# apex-iii-core.net
KiCad netlist of a schematic drawn in EAGLE
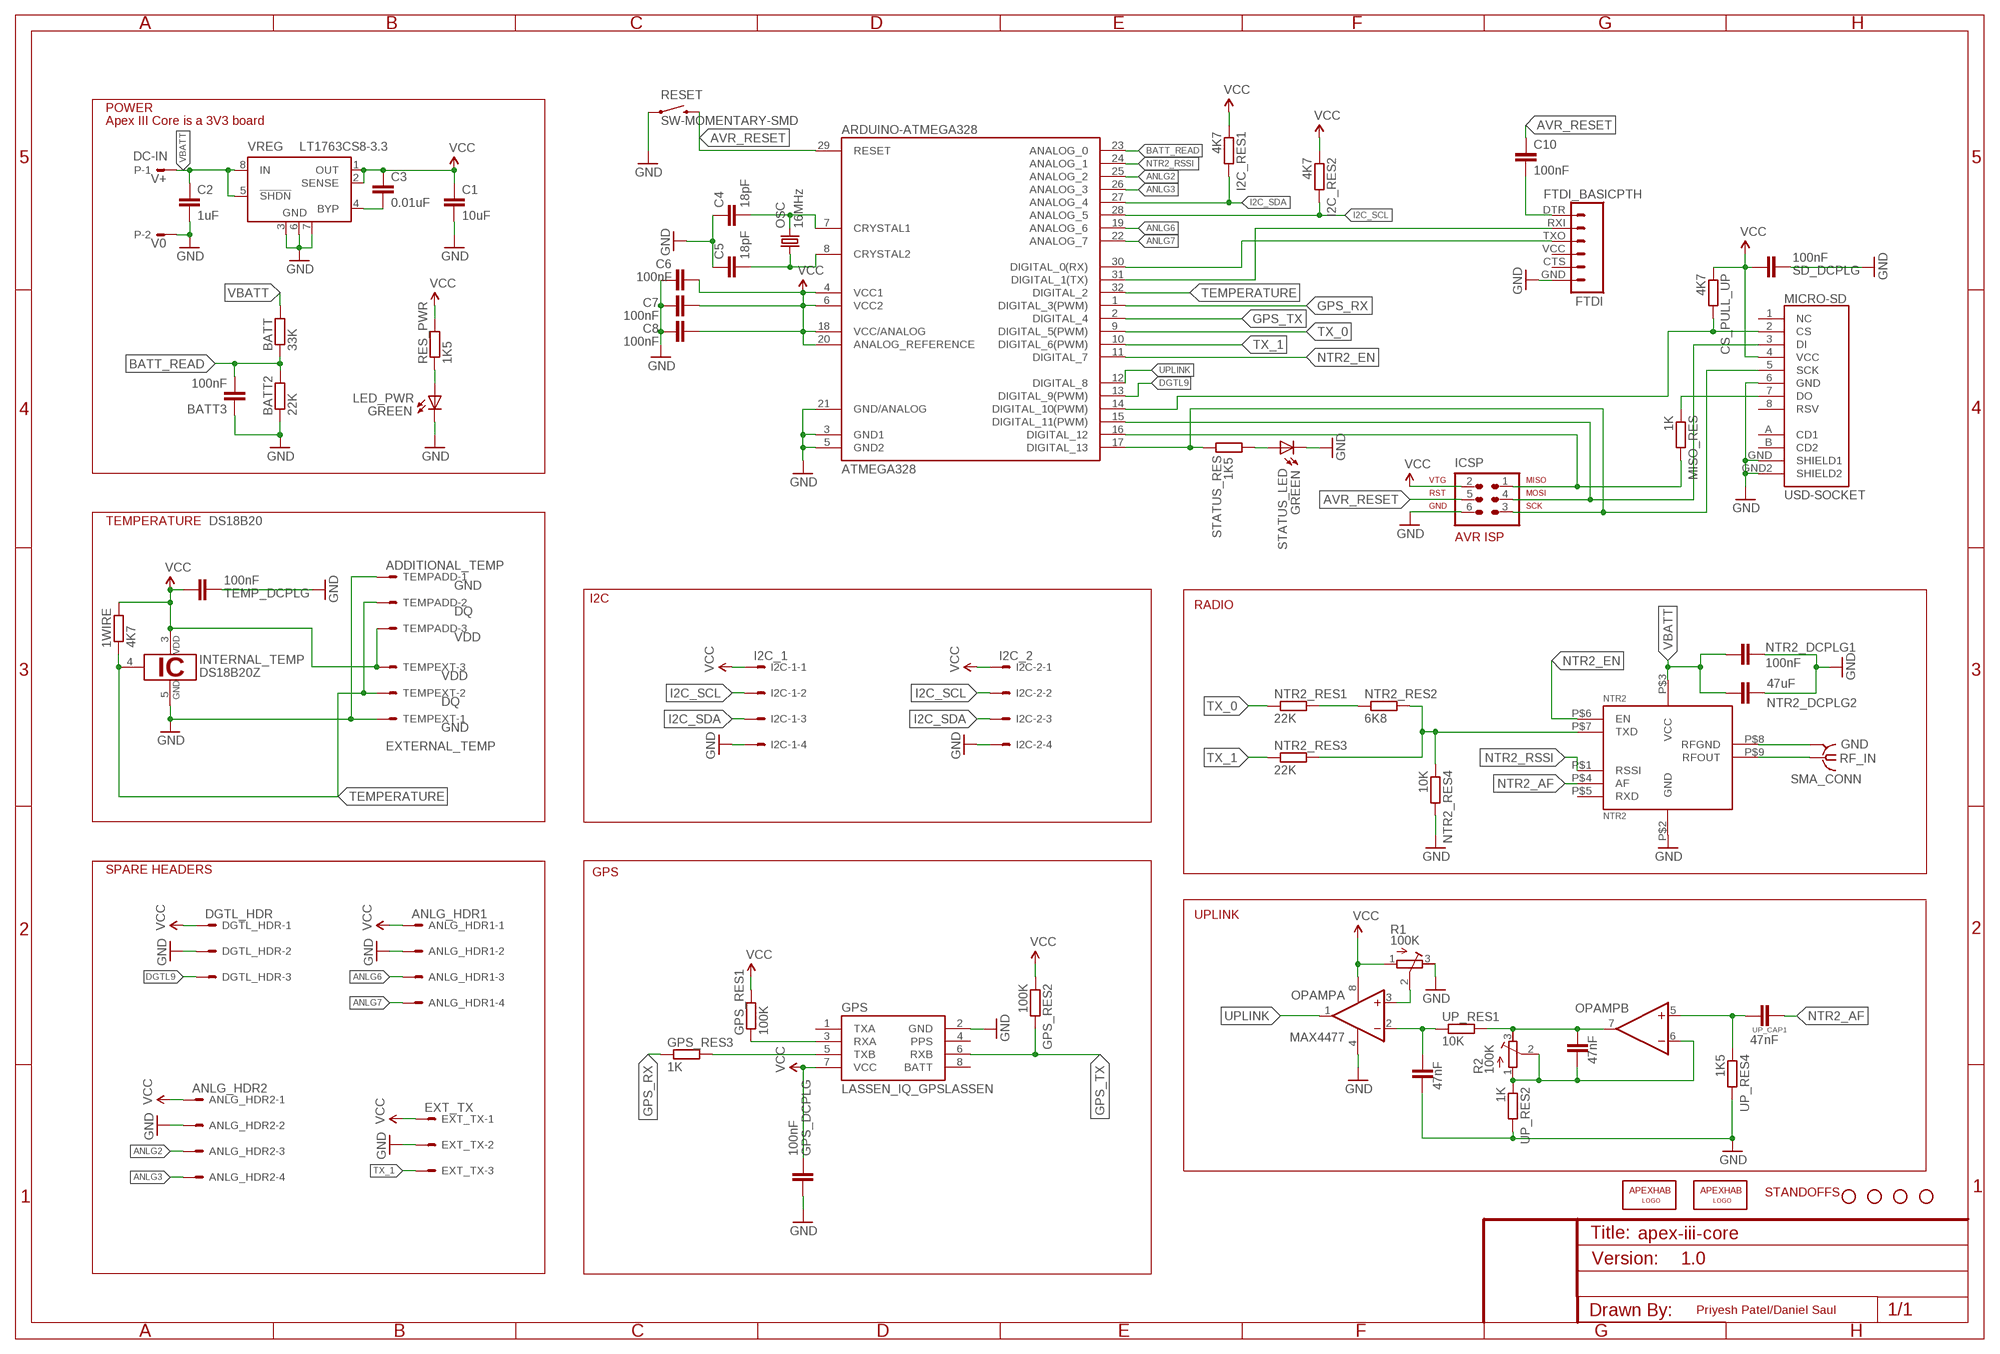
[diagram p0: schematic, sheet 1]

(export (version "E")
  (design (tool "Eeschema 10.0.6"))
  (components
    (comp (ref "1WIRE")
      (value "4K7")
      (footprint "eagle-import:R0805")
      (libsource (lib "eagle-import") (part "R-EU_R0805"))
    )
    (comp (ref "ANLG_HDR1")
      (value "ANLG_HDR1")
      (footprint "eagle-import:6410-04")
      (libsource (lib "eagle-import") (part "22-?-0427-2041"))
    )
    (comp (ref "ANLG_HDR2")
      (value "ANLG_HDR2")
      (footprint "eagle-import:6410-04")
      (libsource (lib "eagle-import") (part "22-?-0427-2041"))
    )
    (comp (ref "ARDUINO-ATMEGA328")
      (value "ATMEGA328")
      (footprint "eagle-import:TQFP32-08")
      (libsource (lib "eagle-import") (part "ATMEGA168-AU"))
    )
    (comp (ref "BATT")
      (value "33K")
      (footprint "eagle-import:R0805")
      (libsource (lib "eagle-import") (part "R-EU_R0805"))
    )
    (comp (ref "BATT2")
      (value "22K")
      (footprint "eagle-import:R0805")
      (libsource (lib "eagle-import") (part "R-EU_R0805"))
    )
    (comp (ref "BATT3")
      (value "100nF")
      (footprint "eagle-import:0805")
      (libsource (lib "eagle-import") (part "CAP0805"))
    )
    (comp (ref "C1")
      (value "10uF")
      (footprint "eagle-import:0805")
      (libsource (lib "eagle-import") (part "CAP0805"))
    )
    (comp (ref "C2")
      (value "1uF")
      (footprint "eagle-import:0805")
      (libsource (lib "eagle-import") (part "CAP0805"))
    )
    (comp (ref "C3")
      (value "0.01uF")
      (footprint "eagle-import:0805")
      (libsource (lib "eagle-import") (part "CAP0805"))
    )
    (comp (ref "C4")
      (value "18pF")
      (footprint "eagle-import:0805")
      (libsource (lib "eagle-import") (part "CAP0805"))
    )
    (comp (ref "C5")
      (value "18pF")
      (footprint "eagle-import:0805")
      (libsource (lib "eagle-import") (part "CAP0805"))
    )
    (comp (ref "C6")
      (value "100nF")
      (footprint "eagle-import:0805")
      (libsource (lib "eagle-import") (part "CAP0805"))
    )
    (comp (ref "C7")
      (value "100nF")
      (footprint "eagle-import:0805")
      (libsource (lib "eagle-import") (part "CAP0805"))
    )
    (comp (ref "C8")
      (value "100nF")
      (footprint "eagle-import:0805")
      (libsource (lib "eagle-import") (part "CAP0805"))
    )
    (comp (ref "C10")
      (value "100nF")
      (footprint "eagle-import:0805")
      (libsource (lib "eagle-import") (part "CAP0805"))
    )
    (comp (ref "CS_PULL_UP")
      (value "4K7")
      (footprint "eagle-import:R0805")
      (libsource (lib "eagle-import") (part "R-EU_R0805"))
    )
    (comp (ref "DGTL_HDR")
      (value "DGTL_HDR")
      (footprint "eagle-import:6410-03")
      (libsource (lib "eagle-import") (part "22-?-0327-2031"))
    )
    (comp (ref "EXT_TX")
      (value "EXT_TX")
      (footprint "eagle-import:6410-03")
      (libsource (lib "eagle-import") (part "22-?-0327-2031"))
    )
    (comp (ref "FTDI")
      (value "FTDI_BASICPTH")
      (footprint "eagle-import:FTDI_BASIC")
      (libsource (lib "eagle-import") (part "FTDI_BASICPTH"))
    )
    (comp (ref "GPS")
      (value "LASSEN_IQ_GPSLASSEN")
      (footprint "eagle-import:LASSEN_IQ_GPS")
      (libsource (lib "eagle-import") (part "LASSEN_IQ_GPSLASSEN"))
    )
    (comp (ref "GPS_DCPLG")
      (value "100nF")
      (footprint "eagle-import:0805")
      (libsource (lib "eagle-import") (part "CAP0805"))
    )
    (comp (ref "GPS_RES1")
      (value "100K")
      (footprint "eagle-import:R0805")
      (libsource (lib "eagle-import") (part "R-EU_R0805"))
    )
    (comp (ref "GPS_RES2")
      (value "100K")
      (footprint "eagle-import:R0805")
      (libsource (lib "eagle-import") (part "R-EU_R0805"))
    )
    (comp (ref "GPS_RES3")
      (value "1K")
      (footprint "eagle-import:R0805")
      (libsource (lib "eagle-import") (part "R-EU_R0805"))
    )
    (comp (ref "I2C-1")
      (value "I2C_1")
      (footprint "eagle-import:6410-04")
      (libsource (lib "eagle-import") (part "22-?-0427-2041"))
    )
    (comp (ref "I2C-2")
      (value "I2C_2")
      (footprint "eagle-import:6410-04")
      (libsource (lib "eagle-import") (part "22-?-0427-2041"))
    )
    (comp (ref "I2C_RES1")
      (value "4K7")
      (footprint "eagle-import:R0805")
      (libsource (lib "eagle-import") (part "R-EU_R0805"))
    )
    (comp (ref "I2C_RES2")
      (value "4K7")
      (footprint "eagle-import:R0805")
      (libsource (lib "eagle-import") (part "R-EU_R0805"))
    )
    (comp (ref "ICSP")
      (value "AVR-ISP-6")
      (footprint "eagle-import:AVR-ISP-6")
      (libsource (lib "eagle-import") (part "AVR-ISP-6"))
    )
    (comp (ref "INTERNAL_TEMP")
      (value "DS18B20Z")
      (footprint "eagle-import:SO08")
      (libsource (lib "eagle-import") (part "DS18B20Z"))
    )
    (comp (ref "JP1")
      (value "STAND-OFF")
      (footprint "eagle-import:STAND-OFF")
      (libsource (lib "eagle-import") (part "STAND-OFF"))
    )
    (comp (ref "JP2")
      (value "STAND-OFF")
      (footprint "eagle-import:STAND-OFF")
      (libsource (lib "eagle-import") (part "STAND-OFF"))
    )
    (comp (ref "JP3")
      (value "STAND-OFF")
      (footprint "eagle-import:STAND-OFF")
      (libsource (lib "eagle-import") (part "STAND-OFF"))
    )
    (comp (ref "JP4")
      (value "STAND-OFF")
      (footprint "eagle-import:STAND-OFF")
      (libsource (lib "eagle-import") (part "STAND-OFF"))
    )
    (comp (ref "JP5")
      (value "APEXHAB-LOGO_APEXHAB-SMALL")
      (footprint "eagle-import:APEXHAB-LOGO-SMALL")
      (libsource (lib "eagle-import") (part "APEXHAB-LOGO_APEXHAB-SMALL"))
    )
    (comp (ref "JP6")
      (value "APEXHAB-LOGO_APEXHAB")
      (footprint "eagle-import:APEXHAB-LOGO")
      (libsource (lib "eagle-import") (part "APEXHAB-LOGO_APEXHAB"))
    )
    (comp (ref "LED_PWR")
      (value "GREEN")
      (footprint "eagle-import:CHIPLED_0603")
      (libsource (lib "eagle-import") (part "LEDCHIPLED_0603"))
    )
    (comp (ref "MICRO-SD")
      (value "USD-SOCKET")
      (footprint "eagle-import:MICRO-SD-PUSH-PULL")
      (libsource (lib "eagle-import") (part "USD-SOCKET"))
    )
    (comp (ref "MISO_RES")
      (value "1K")
      (footprint "eagle-import:R0805")
      (libsource (lib "eagle-import") (part "R-EU_R0805"))
    )
    (comp (ref "NTR2")
      (value "NTR2")
      (footprint "eagle-import:NTR2")
      (libsource (lib "eagle-import") (part "NTR2"))
    )
    (comp (ref "NTR2_DCPLG1")
      (value "100nF")
      (footprint "eagle-import:0805")
      (libsource (lib "eagle-import") (part "CAP0805"))
    )
    (comp (ref "NTR2_DCPLG2")
      (value "47uF")
      (footprint "eagle-import:0805")
      (libsource (lib "eagle-import") (part "CAP0805"))
    )
    (comp (ref "NTR2_RES1")
      (value "22K")
      (footprint "eagle-import:R0805")
      (libsource (lib "eagle-import") (part "R-EU_R0805"))
    )
    (comp (ref "NTR2_RES2")
      (value "6K8")
      (footprint "eagle-import:R0805")
      (libsource (lib "eagle-import") (part "R-EU_R0805"))
    )
    (comp (ref "NTR2_RES3")
      (value "22K")
      (footprint "eagle-import:R0805")
      (libsource (lib "eagle-import") (part "R-EU_R0805"))
    )
    (comp (ref "NTR2_RES4")
      (value "10K")
      (footprint "eagle-import:R0805")
      (libsource (lib "eagle-import") (part "R-EU_R0805"))
    )
    (comp (ref "OPAMP")
      (value "MAX4477")
      (footprint "eagle-import:SO08")
      (libsource (lib "eagle-import") (part "CA3240ED"))
    )
    (comp (ref "OSC")
      (value "16MHz")
      (footprint "eagle-import:CRYSTAL-SMD-5X3")
      (libsource (lib "eagle-import") (part "CRYSTAL5X3"))
    )
    (comp (ref "P")
      (value "DC-IN")
      (footprint "eagle-import:6410-02")
      (libsource (lib "eagle-import") (part "22-?-0227-2021"))
    )
    (comp (ref "R1")
      (value "100K")
      (footprint "eagle-import:RTRIM3214W")
      (libsource (lib "eagle-import") (part "R-TRIMM3214W"))
    )
    (comp (ref "R2")
      (value "100K")
      (footprint "eagle-import:RTRIM3214W")
      (libsource (lib "eagle-import") (part "R-TRIMM3214W"))
    )
    (comp (ref "RESET")
      (value "SW-MOMENTARY-SMD")
      (footprint "eagle-import:TACTILE-SWITCH-1101NE")
      (libsource (lib "eagle-import") (part "SWITCH-MOMENTARY-2-SMD-1101NE"))
    )
    (comp (ref "RES_PWR")
      (value "1K5")
      (footprint "eagle-import:R0805")
      (libsource (lib "eagle-import") (part "R-EU_R0805"))
    )
    (comp (ref "SD_DCPLG")
      (value "100nF")
      (footprint "eagle-import:0805")
      (libsource (lib "eagle-import") (part "CAP0805"))
    )
    (comp (ref "SMA_CONN")
      (value "SMA-142-0701-801/806")
      (footprint "eagle-import:J502-ND-142-0701-801_806")
      (fields (field (name "MF") "JOHNSON COMPONENTS") (field (name "MPN") "142-0701-801"))
      (libsource (lib "eagle-import") (part "SMA-142-0701-801/806"))
    )
    (comp (ref "STATUS_LED")
      (value "GREEN")
      (footprint "eagle-import:CHIPLED_0603")
      (libsource (lib "eagle-import") (part "LEDCHIPLED_0603"))
    )
    (comp (ref "STATUS_RES")
      (value "1K5")
      (footprint "eagle-import:R0805")
      (libsource (lib "eagle-import") (part "R-EU_R0805"))
    )
    (comp (ref "TEMPADD")
      (value "ADDITIONAL_TEMP")
      (footprint "eagle-import:6410-03")
      (libsource (lib "eagle-import") (part "con-molex_22-?-0327-2031"))
    )
    (comp (ref "TEMPEXT")
      (value "EXTERNAL_TEMP")
      (footprint "eagle-import:6410-03")
      (libsource (lib "eagle-import") (part "con-molex_22-?-0327-2031"))
    )
    (comp (ref "TEMP_DCPLG")
      (value "100nF")
      (footprint "eagle-import:0805")
      (libsource (lib "eagle-import") (part "CAP0805"))
    )
    (comp (ref "UP_CAP1")
      (value "47nF")
      (footprint "eagle-import:0805")
      (libsource (lib "eagle-import") (part "CAP0805"))
    )
    (comp (ref "UP_CAP3")
      (value "47nF")
      (footprint "eagle-import:0805")
      (libsource (lib "eagle-import") (part "CAP0805"))
    )
    (comp (ref "UP_CAP4")
      (value "47nF")
      (footprint "eagle-import:0805")
      (libsource (lib "eagle-import") (part "CAP0805"))
    )
    (comp (ref "UP_RES1")
      (value "10K")
      (footprint "eagle-import:R0805")
      (libsource (lib "eagle-import") (part "R-EU_R0805"))
    )
    (comp (ref "UP_RES2")
      (value "1K")
      (footprint "eagle-import:R0805")
      (libsource (lib "eagle-import") (part "R-EU_R0805"))
    )
    (comp (ref "UP_RES4")
      (value "1K5")
      (footprint "eagle-import:R0805")
      (libsource (lib "eagle-import") (part "R-EU_R0805"))
    )
    (comp (ref "VREG")
      (value "LT1763CS8-3.3")
      (footprint "eagle-import:SOIC8")
      (libsource (lib "eagle-import") (part "LT1763CS8-3.3"))
    )
  )
  (nets
    (net (code "1") (name "/BATT") (class "Default")
      (node (ref "GPS") (pin "8") (pinfunction "BATT_8") (pintype "power_in"))
    )
    (net (code "2") (name "/RF_IN") (class "Default")
      (node (ref "NTR2") (pin "P$9") (pinfunction "RFOUT_P$9") (pintype "bidirectional"))
      (node (ref "SMA_CONN") (pin "1") (pinfunction "1_1") (pintype "passive"))
    )
    (net (code "3") (name "ANLG2") (class "Default")
      (node (ref "ANLG_HDR2") (pin "3") (pinfunction "S_3") (pintype "passive"))
      (node (ref "ARDUINO-ATMEGA328") (pin "25") (pinfunction "ANALOG_2_25") (pintype "bidirectional"))
    )
    (net (code "4") (name "ANLG3") (class "Default")
      (node (ref "ANLG_HDR2") (pin "4") (pinfunction "S_4") (pintype "passive"))
      (node (ref "ARDUINO-ATMEGA328") (pin "26") (pinfunction "ANALOG_3_26") (pintype "bidirectional"))
    )
    (net (code "5") (name "ANLG6") (class "Default")
      (node (ref "ANLG_HDR1") (pin "3") (pinfunction "S_3") (pintype "passive"))
      (node (ref "ARDUINO-ATMEGA328") (pin "19") (pinfunction "ANALOG_6_19") (pintype "passive"))
    )
    (net (code "6") (name "ANLG7") (class "Default")
      (node (ref "ANLG_HDR1") (pin "4") (pinfunction "S_4") (pintype "passive"))
      (node (ref "ARDUINO-ATMEGA328") (pin "22") (pinfunction "ANALOG_7_22") (pintype "passive"))
    )
    (net (code "7") (name "AVR_RESET") (class "Default")
      (node (ref "ARDUINO-ATMEGA328") (pin "29") (pinfunction "RESET_29") (pintype "bidirectional"))
      (node (ref "C10") (pin "1") (pinfunction "1_1") (pintype "passive"))
      (node (ref "ICSP") (pin "5") (pinfunction "5_5") (pintype "passive"))
      (node (ref "RESET") (pin "P$2") (pinfunction "2_P$2") (pintype "passive"))
    )
    (net (code "8") (name "BATT_READ") (class "Default")
      (node (ref "ARDUINO-ATMEGA328") (pin "23") (pinfunction "ANALOG_0_23") (pintype "bidirectional"))
      (node (ref "BATT") (pin "1") (pinfunction "1_1") (pintype "passive"))
      (node (ref "BATT2") (pin "2") (pinfunction "2_2") (pintype "passive"))
      (node (ref "BATT3") (pin "2") (pinfunction "2_2") (pintype "passive"))
    )
    (net (code "9") (name "DGTL9") (class "Default")
      (node (ref "ARDUINO-ATMEGA328") (pin "13") (pinfunction "DIGITAL_9(PWM)_13") (pintype "bidirectional"))
      (node (ref "DGTL_HDR") (pin "3") (pinfunction "S_3") (pintype "passive"))
    )
    (net (code "10") (name "GND") (class "Default")
      (node (ref "ANLG_HDR1") (pin "2") (pinfunction "S_2") (pintype "passive"))
      (node (ref "ANLG_HDR2") (pin "2") (pinfunction "S_2") (pintype "passive"))
      (node (ref "ARDUINO-ATMEGA328") (pin "21") (pinfunction "GND/ANALOG_21") (pintype "power_in"))
      (node (ref "ARDUINO-ATMEGA328") (pin "3") (pinfunction "GND1_3") (pintype "power_in"))
      (node (ref "ARDUINO-ATMEGA328") (pin "5") (pinfunction "GND2_5") (pintype "power_in"))
      (node (ref "BATT2") (pin "1") (pinfunction "1_1") (pintype "passive"))
      (node (ref "BATT3") (pin "1") (pinfunction "1_1") (pintype "passive"))
      (node (ref "C1") (pin "2") (pinfunction "2_2") (pintype "passive"))
      (node (ref "C2") (pin "2") (pinfunction "2_2") (pintype "passive"))
      (node (ref "C4") (pin "1") (pinfunction "1_1") (pintype "passive"))
      (node (ref "C5") (pin "1") (pinfunction "1_1") (pintype "passive"))
      (node (ref "C6") (pin "1") (pinfunction "1_1") (pintype "passive"))
      (node (ref "C7") (pin "1") (pinfunction "1_1") (pintype "passive"))
      (node (ref "C8") (pin "1") (pinfunction "1_1") (pintype "passive"))
      (node (ref "DGTL_HDR") (pin "2") (pinfunction "S_2") (pintype "passive"))
      (node (ref "EXT_TX") (pin "2") (pinfunction "S_2") (pintype "passive"))
      (node (ref "FTDI") (pin "GND") (pinfunction "6_GND") (pintype "passive"))
      (node (ref "GPS") (pin "2") (pinfunction "GND_2") (pintype "power_in"))
      (node (ref "GPS_DCPLG") (pin "2") (pinfunction "2_2") (pintype "passive"))
      (node (ref "I2C-1") (pin "4") (pinfunction "S_4") (pintype "passive"))
      (node (ref "I2C-2") (pin "4") (pinfunction "S_4") (pintype "passive"))
      (node (ref "ICSP") (pin "6") (pinfunction "6_6") (pintype "passive"))
      (node (ref "INTERNAL_TEMP") (pin "5") (pinfunction "GND_5") (pintype "power_in"))
      (node (ref "LED_PWR") (pin "C") (pinfunction "C_C") (pintype "passive"))
      (node (ref "MICRO-SD") (pin "6") (pinfunction "GND_6") (pintype "bidirectional"))
      (node (ref "MICRO-SD") (pin "GND") (pinfunction "SHIELD1_GND") (pintype "bidirectional"))
      (node (ref "MICRO-SD") (pin "GND2") (pinfunction "SHIELD2_GND2") (pintype "bidirectional"))
      (node (ref "NTR2") (pin "P$2") (pinfunction "GND_P$2") (pintype "power_in"))
      (node (ref "NTR2") (pin "P$8") (pinfunction "RFGND_P$8") (pintype "bidirectional"))
      (node (ref "NTR2_DCPLG1") (pin "1") (pinfunction "1_1") (pintype "passive"))
      (node (ref "NTR2_DCPLG2") (pin "1") (pinfunction "1_1") (pintype "passive"))
      (node (ref "NTR2_RES4") (pin "2") (pinfunction "2_2") (pintype "passive"))
      (node (ref "OPAMP") (pin "4") (pinfunction "V-_4") (pintype "power_in"))
      (node (ref "P") (pin "2") (pinfunction "S_2") (pintype "passive"))
      (node (ref "R1") (pin "3") (pinfunction "A_3") (pintype "passive"))
      (node (ref "RESET") (pin "P$1") (pinfunction "1_P$1") (pintype "passive"))
      (node (ref "SD_DCPLG") (pin "1") (pinfunction "1_1") (pintype "passive"))
      (node (ref "SMA_CONN") (pin "G@1") (pinfunction "GND_G@1") (pintype "power_in"))
      (node (ref "STATUS_LED") (pin "C") (pinfunction "C_C") (pintype "passive"))
      (node (ref "TEMPADD") (pin "1") (pinfunction "S_1") (pintype "passive"))
      (node (ref "TEMPEXT") (pin "1") (pinfunction "S_1") (pintype "passive"))
      (node (ref "TEMP_DCPLG") (pin "1") (pinfunction "1_1") (pintype "passive"))
      (node (ref "UP_CAP4") (pin "2") (pinfunction "2_2") (pintype "passive"))
      (node (ref "UP_RES2") (pin "2") (pinfunction "2_2") (pintype "passive"))
      (node (ref "UP_RES4") (pin "2") (pinfunction "2_2") (pintype "passive"))
      (node (ref "VREG") (pin "3") (pinfunction "GND_3") (pintype "power_in"))
      (node (ref "VREG") (pin "6") (pinfunction "GND_6") (pintype "power_in"))
      (node (ref "VREG") (pin "7") (pinfunction "GND_7") (pintype "power_in"))
    )
    (net (code "11") (name "GPS_RX") (class "Default")
      (node (ref "ARDUINO-ATMEGA328") (pin "1") (pinfunction "DIGITAL_3(PWM)_1") (pintype "bidirectional"))
      (node (ref "GPS_RES3") (pin "1") (pinfunction "1_1") (pintype "passive"))
    )
    (net (code "12") (name "GPS_TX") (class "Default")
      (node (ref "ARDUINO-ATMEGA328") (pin "2") (pinfunction "DIGITAL_4_2") (pintype "bidirectional"))
      (node (ref "GPS") (pin "6") (pinfunction "RXB_6") (pintype "input"))
      (node (ref "GPS_RES2") (pin "2") (pinfunction "2_2") (pintype "passive"))
    )
    (net (code "13") (name "I2C_SCL") (class "Default")
      (node (ref "ARDUINO-ATMEGA328") (pin "28") (pinfunction "ANALOG_5_28") (pintype "bidirectional"))
      (node (ref "I2C-1") (pin "2") (pinfunction "S_2") (pintype "passive"))
      (node (ref "I2C-2") (pin "2") (pinfunction "S_2") (pintype "passive"))
      (node (ref "I2C_RES2") (pin "2") (pinfunction "2_2") (pintype "passive"))
    )
    (net (code "14") (name "I2C_SDA") (class "Default")
      (node (ref "ARDUINO-ATMEGA328") (pin "27") (pinfunction "ANALOG_4_27") (pintype "bidirectional"))
      (node (ref "I2C-1") (pin "3") (pinfunction "S_3") (pintype "passive"))
      (node (ref "I2C-2") (pin "3") (pinfunction "S_3") (pintype "passive"))
      (node (ref "I2C_RES1") (pin "2") (pinfunction "2_2") (pintype "passive"))
    )
    (net (code "15") (name "NTR2_AF") (class "Default")
      (node (ref "NTR2") (pin "P$4") (pinfunction "AF_P$4") (pintype "bidirectional"))
      (node (ref "UP_CAP1") (pin "1") (pinfunction "1_1") (pintype "passive"))
    )
    (net (code "16") (name "NTR2_EN") (class "Default")
      (node (ref "ARDUINO-ATMEGA328") (pin "11") (pinfunction "DIGITAL_7_11") (pintype "bidirectional"))
      (node (ref "NTR2") (pin "P$6") (pinfunction "EN_P$6") (pintype "bidirectional"))
    )
    (net (code "17") (name "NTR2_RSSI") (class "Default")
      (node (ref "ARDUINO-ATMEGA328") (pin "24") (pinfunction "ANALOG_1_24") (pintype "bidirectional"))
      (node (ref "NTR2") (pin "P$1") (pinfunction "RSSI_P$1") (pintype "bidirectional"))
    )
    (net (code "18") (name "Net-(ARDUINO-ATMEGA328-CRYSTAL1)") (class "Default")
      (node (ref "ARDUINO-ATMEGA328") (pin "7") (pinfunction "CRYSTAL1_7") (pintype "bidirectional"))
      (node (ref "C4") (pin "2") (pinfunction "2_2") (pintype "passive"))
      (node (ref "OSC") (pin "3") (pinfunction "2_3") (pintype "passive"))
    )
    (net (code "19") (name "Net-(ARDUINO-ATMEGA328-CRYSTAL2)") (class "Default")
      (node (ref "ARDUINO-ATMEGA328") (pin "8") (pinfunction "CRYSTAL2_8") (pintype "bidirectional"))
      (node (ref "C5") (pin "2") (pinfunction "2_2") (pintype "passive"))
      (node (ref "OSC") (pin "1") (pinfunction "1_1") (pintype "passive"))
    )
    (net (code "20") (name "Net-(ARDUINO-ATMEGA328-DIGITAL_0(RX))") (class "Default")
      (node (ref "ARDUINO-ATMEGA328") (pin "30") (pinfunction "DIGITAL_0(RX)_30") (pintype "bidirectional"))
      (node (ref "FTDI") (pin "TXO") (pinfunction "3_TXO") (pintype "passive"))
    )
    (net (code "21") (name "Net-(ARDUINO-ATMEGA328-DIGITAL_1(TX))") (class "Default")
      (node (ref "ARDUINO-ATMEGA328") (pin "31") (pinfunction "DIGITAL_1(TX)_31") (pintype "bidirectional"))
      (node (ref "FTDI") (pin "RXI") (pinfunction "2_RXI") (pintype "passive"))
    )
    (net (code "22") (name "Net-(ARDUINO-ATMEGA328-DIGITAL_10(PWM))") (class "Default")
      (node (ref "ARDUINO-ATMEGA328") (pin "14") (pinfunction "DIGITAL_10(PWM)_14") (pintype "bidirectional"))
      (node (ref "CS_PULL_UP") (pin "2") (pinfunction "2_2") (pintype "passive"))
      (node (ref "MICRO-SD") (pin "2") (pinfunction "CS_2") (pintype "bidirectional"))
    )
    (net (code "23") (name "Net-(ARDUINO-ATMEGA328-DIGITAL_11(PWM))") (class "Default")
      (node (ref "ARDUINO-ATMEGA328") (pin "15") (pinfunction "DIGITAL_11(PWM)_15") (pintype "bidirectional"))
      (node (ref "ICSP") (pin "4") (pinfunction "4_4") (pintype "passive"))
      (node (ref "MICRO-SD") (pin "3") (pinfunction "DI_3") (pintype "bidirectional"))
    )
    (net (code "24") (name "Net-(ARDUINO-ATMEGA328-DIGITAL_12)") (class "Default")
      (node (ref "ARDUINO-ATMEGA328") (pin "16") (pinfunction "DIGITAL_12_16") (pintype "bidirectional"))
      (node (ref "ICSP") (pin "1") (pinfunction "1_1") (pintype "passive"))
      (node (ref "MISO_RES") (pin "2") (pinfunction "2_2") (pintype "passive"))
    )
    (net (code "25") (name "Net-(ARDUINO-ATMEGA328-DIGITAL_13)") (class "Default")
      (node (ref "ARDUINO-ATMEGA328") (pin "17") (pinfunction "DIGITAL_13_17") (pintype "bidirectional"))
      (node (ref "ICSP") (pin "3") (pinfunction "3_3") (pintype "passive"))
      (node (ref "MICRO-SD") (pin "5") (pinfunction "SCK_5") (pintype "bidirectional"))
      (node (ref "STATUS_RES") (pin "1") (pinfunction "1_1") (pintype "passive"))
    )
    (net (code "26") (name "Net-(FTDI-1)") (class "Default")
      (node (ref "C10") (pin "2") (pinfunction "2_2") (pintype "passive"))
      (node (ref "FTDI") (pin "DTR") (pinfunction "1_DTR") (pintype "passive"))
    )
    (net (code "27") (name "Net-(GPS-RXA)") (class "Default")
      (node (ref "GPS") (pin "3") (pinfunction "RXA_3") (pintype "input"))
      (node (ref "GPS_RES1") (pin "1") (pinfunction "1_1") (pintype "passive"))
    )
    (net (code "28") (name "Net-(GPS-TXB)") (class "Default")
      (node (ref "GPS") (pin "5") (pinfunction "TXB_5") (pintype "output"))
      (node (ref "GPS_RES3") (pin "2") (pinfunction "2_2") (pintype "passive"))
    )
    (net (code "29") (name "Net-(LED_PWR-PadA)") (class "Default")
      (node (ref "LED_PWR") (pin "A") (pinfunction "A_A") (pintype "passive"))
      (node (ref "RES_PWR") (pin "1") (pinfunction "1_1") (pintype "passive"))
    )
    (net (code "30") (name "Net-(MICRO-SD-DO)") (class "Default")
      (node (ref "MICRO-SD") (pin "7") (pinfunction "DO_7") (pintype "bidirectional"))
      (node (ref "MISO_RES") (pin "1") (pinfunction "1_1") (pintype "passive"))
    )
    (net (code "31") (name "Net-(NTR2-TXD)") (class "Default")
      (node (ref "NTR2") (pin "P$7") (pinfunction "TXD_P$7") (pintype "bidirectional"))
      (node (ref "NTR2_RES2") (pin "2") (pinfunction "2_2") (pintype "passive"))
      (node (ref "NTR2_RES3") (pin "2") (pinfunction "2_2") (pintype "passive"))
      (node (ref "NTR2_RES4") (pin "1") (pinfunction "1_1") (pintype "passive"))
    )
    (net (code "32") (name "Net-(NTR2_RES1-Pad2)") (class "Default")
      (node (ref "NTR2_RES1") (pin "2") (pinfunction "2_2") (pintype "passive"))
      (node (ref "NTR2_RES2") (pin "1") (pinfunction "1_1") (pintype "passive"))
    )
    (net (code "33") (name "Net-(OPAMPA-+IN)") (class "Default")
      (node (ref "OPAMP") (pin "3") (pinfunction "+IN_3") (pintype "input"))
      (node (ref "R1") (pin "2") (pinfunction "S_2") (pintype "passive"))
    )
    (net (code "34") (name "Net-(OPAMPA--IN)") (class "Default")
      (node (ref "OPAMP") (pin "2") (pinfunction "-IN_2") (pintype "input"))
      (node (ref "UP_CAP4") (pin "1") (pinfunction "1_1") (pintype "passive"))
      (node (ref "UP_RES1") (pin "1") (pinfunction "1_1") (pintype "passive"))
    )
    (net (code "35") (name "Net-(OPAMPB-+IN)") (class "Default")
      (node (ref "OPAMP") (pin "5") (pinfunction "+IN_5") (pintype "input"))
      (node (ref "UP_CAP1") (pin "2") (pinfunction "2_2") (pintype "passive"))
      (node (ref "UP_RES4") (pin "1") (pinfunction "1_1") (pintype "passive"))
    )
    (net (code "36") (name "Net-(OPAMPB--IN)") (class "Default")
      (node (ref "OPAMP") (pin "6") (pinfunction "-IN_6") (pintype "input"))
      (node (ref "R2") (pin "1") (pinfunction "E_1") (pintype "passive"))
      (node (ref "R2") (pin "2") (pinfunction "S_2") (pintype "passive"))
      (node (ref "UP_CAP3") (pin "2") (pinfunction "2_2") (pintype "passive"))
      (node (ref "UP_RES2") (pin "1") (pinfunction "1_1") (pintype "passive"))
    )
    (net (code "37") (name "Net-(OPAMPB-OUT)") (class "Default")
      (node (ref "OPAMP") (pin "7") (pinfunction "OUT_7") (pintype "output"))
      (node (ref "R2") (pin "3") (pinfunction "A_3") (pintype "passive"))
      (node (ref "UP_CAP3") (pin "1") (pinfunction "1_1") (pintype "passive"))
      (node (ref "UP_RES1") (pin "2") (pinfunction "2_2") (pintype "passive"))
    )
    (net (code "38") (name "Net-(STATUS_LED-PadA)") (class "Default")
      (node (ref "STATUS_LED") (pin "A") (pinfunction "A_A") (pintype "passive"))
      (node (ref "STATUS_RES") (pin "2") (pinfunction "2_2") (pintype "passive"))
    )
    (net (code "39") (name "Net-(VREG-BYP)") (class "Default")
      (node (ref "C3") (pin "2") (pinfunction "2_2") (pintype "passive"))
      (node (ref "VREG") (pin "4") (pinfunction "BYP_4") (pintype "input"))
    )
    (net (code "40") (name "TEMPERATURE") (class "Default")
      (node (ref "1WIRE") (pin "1") (pinfunction "1_1") (pintype "passive"))
      (node (ref "ARDUINO-ATMEGA328") (pin "32") (pinfunction "DIGITAL_2_32") (pintype "bidirectional"))
      (node (ref "INTERNAL_TEMP") (pin "4") (pinfunction "1W_4") (pintype "power_in"))
      (node (ref "TEMPADD") (pin "2") (pinfunction "S_2") (pintype "passive"))
      (node (ref "TEMPEXT") (pin "2") (pinfunction "S_2") (pintype "passive"))
    )
    (net (code "41") (name "TX_0") (class "Default")
      (node (ref "ARDUINO-ATMEGA328") (pin "9") (pinfunction "DIGITAL_5(PWM)_9") (pintype "bidirectional"))
      (node (ref "NTR2_RES1") (pin "1") (pinfunction "1_1") (pintype "passive"))
    )
    (net (code "42") (name "TX_1") (class "Default")
      (node (ref "ARDUINO-ATMEGA328") (pin "10") (pinfunction "DIGITAL_6(PWM)_10") (pintype "bidirectional"))
      (node (ref "EXT_TX") (pin "3") (pinfunction "S_3") (pintype "passive"))
      (node (ref "NTR2_RES3") (pin "1") (pinfunction "1_1") (pintype "passive"))
    )
    (net (code "43") (name "UPLINK") (class "Default")
      (node (ref "ARDUINO-ATMEGA328") (pin "12") (pinfunction "DIGITAL_8_12") (pintype "bidirectional"))
      (node (ref "OPAMP") (pin "1") (pinfunction "OUT_1") (pintype "output"))
    )
    (net (code "44") (name "VBATT") (class "Default")
      (node (ref "BATT") (pin "2") (pinfunction "2_2") (pintype "passive"))
      (node (ref "C2") (pin "1") (pinfunction "1_1") (pintype "passive"))
      (node (ref "NTR2") (pin "P$3") (pinfunction "VCC_P$3") (pintype "power_in"))
      (node (ref "NTR2_DCPLG1") (pin "2") (pinfunction "2_2") (pintype "passive"))
      (node (ref "NTR2_DCPLG2") (pin "2") (pinfunction "2_2") (pintype "passive"))
      (node (ref "P") (pin "1") (pinfunction "S_1") (pintype "passive"))
      (node (ref "VREG") (pin "5") (pinfunction "~{SHDN}_5") (pintype "input"))
      (node (ref "VREG") (pin "8") (pinfunction "IN_8") (pintype "input"))
    )
    (net (code "45") (name "VCC") (class "Default")
      (node (ref "1WIRE") (pin "2") (pinfunction "2_2") (pintype "passive"))
      (node (ref "ANLG_HDR1") (pin "1") (pinfunction "S_1") (pintype "passive"))
      (node (ref "ANLG_HDR2") (pin "1") (pinfunction "S_1") (pintype "passive"))
      (node (ref "ARDUINO-ATMEGA328") (pin "18") (pinfunction "VCC/ANALOG_18") (pintype "passive"))
      (node (ref "ARDUINO-ATMEGA328") (pin "20") (pinfunction "ANALOG_REFERENCE_20") (pintype "passive"))
      (node (ref "ARDUINO-ATMEGA328") (pin "4") (pinfunction "VCC1_4") (pintype "power_in"))
      (node (ref "ARDUINO-ATMEGA328") (pin "6") (pinfunction "VCC2_6") (pintype "power_in"))
      (node (ref "C1") (pin "1") (pinfunction "1_1") (pintype "passive"))
      (node (ref "C3") (pin "1") (pinfunction "1_1") (pintype "passive"))
      (node (ref "C6") (pin "2") (pinfunction "2_2") (pintype "passive"))
      (node (ref "C7") (pin "2") (pinfunction "2_2") (pintype "passive"))
      (node (ref "C8") (pin "2") (pinfunction "2_2") (pintype "passive"))
      (node (ref "CS_PULL_UP") (pin "1") (pinfunction "1_1") (pintype "passive"))
      (node (ref "DGTL_HDR") (pin "1") (pinfunction "S_1") (pintype "passive"))
      (node (ref "EXT_TX") (pin "1") (pinfunction "S_1") (pintype "passive"))
      (node (ref "GPS") (pin "7") (pinfunction "VCC_7") (pintype "power_in"))
      (node (ref "GPS_DCPLG") (pin "1") (pinfunction "1_1") (pintype "passive"))
      (node (ref "GPS_RES1") (pin "2") (pinfunction "2_2") (pintype "passive"))
      (node (ref "GPS_RES2") (pin "1") (pinfunction "1_1") (pintype "passive"))
      (node (ref "I2C-1") (pin "1") (pinfunction "S_1") (pintype "passive"))
      (node (ref "I2C-2") (pin "1") (pinfunction "S_1") (pintype "passive"))
      (node (ref "I2C_RES1") (pin "1") (pinfunction "1_1") (pintype "passive"))
      (node (ref "I2C_RES2") (pin "1") (pinfunction "1_1") (pintype "passive"))
      (node (ref "ICSP") (pin "2") (pinfunction "2_2") (pintype "passive"))
      (node (ref "INTERNAL_TEMP") (pin "3") (pinfunction "VDD_3") (pintype "power_in"))
      (node (ref "MICRO-SD") (pin "4") (pinfunction "VCC_4") (pintype "bidirectional"))
      (node (ref "OPAMP") (pin "8") (pinfunction "V+_8") (pintype "power_in"))
      (node (ref "R1") (pin "1") (pinfunction "E_1") (pintype "passive"))
      (node (ref "RES_PWR") (pin "2") (pinfunction "2_2") (pintype "passive"))
      (node (ref "SD_DCPLG") (pin "2") (pinfunction "2_2") (pintype "passive"))
      (node (ref "TEMPADD") (pin "3") (pinfunction "S_3") (pintype "passive"))
      (node (ref "TEMPEXT") (pin "3") (pinfunction "S_3") (pintype "passive"))
      (node (ref "TEMP_DCPLG") (pin "2") (pinfunction "2_2") (pintype "passive"))
      (node (ref "VREG") (pin "1") (pinfunction "OUT_1") (pintype "passive"))
      (node (ref "VREG") (pin "2") (pinfunction "SENSE_2") (pintype "input"))
    )
    (net (code "46") (name "unconnected-(FTDI-4-PadVCC)") (class "Default")
      (node (ref "FTDI") (pin "VCC") (pinfunction "4_VCC") (pintype "passive"))
    )
    (net (code "47") (name "unconnected-(FTDI-5-PadCTS)") (class "Default")
      (node (ref "FTDI") (pin "CTS") (pinfunction "5_CTS") (pintype "passive"))
    )
    (net (code "48") (name "unconnected-(GPS-PPS-Pad4)") (class "Default")
      (node (ref "GPS") (pin "4") (pinfunction "PPS_4") (pintype "output"))
    )
    (net (code "49") (name "unconnected-(GPS-TXA-Pad1)") (class "Default")
      (node (ref "GPS") (pin "1") (pinfunction "TXA_1") (pintype "output"))
    )
    (net (code "50") (name "unconnected-(MICRO-SD-CD1-PadA)") (class "Default")
      (node (ref "MICRO-SD") (pin "A") (pinfunction "CD1_A") (pintype "bidirectional"))
    )
    (net (code "51") (name "unconnected-(MICRO-SD-CD2-PadB)") (class "Default")
      (node (ref "MICRO-SD") (pin "B") (pinfunction "CD2_B") (pintype "bidirectional"))
    )
    (net (code "52") (name "unconnected-(MICRO-SD-NC-Pad1)") (class "Default")
      (node (ref "MICRO-SD") (pin "1") (pinfunction "NC_1") (pintype "bidirectional"))
    )
    (net (code "53") (name "unconnected-(MICRO-SD-RSV-Pad8)") (class "Default")
      (node (ref "MICRO-SD") (pin "8") (pinfunction "RSV_8") (pintype "bidirectional"))
    )
    (net (code "54") (name "unconnected-(NTR2-RXD-PadP$5)") (class "Default")
      (node (ref "NTR2") (pin "P$5") (pinfunction "RXD_P$5") (pintype "bidirectional"))
    )
  )
)
